# frequency_divider_1_3.net
KiCad netlist of a schematic drawn in EAGLE
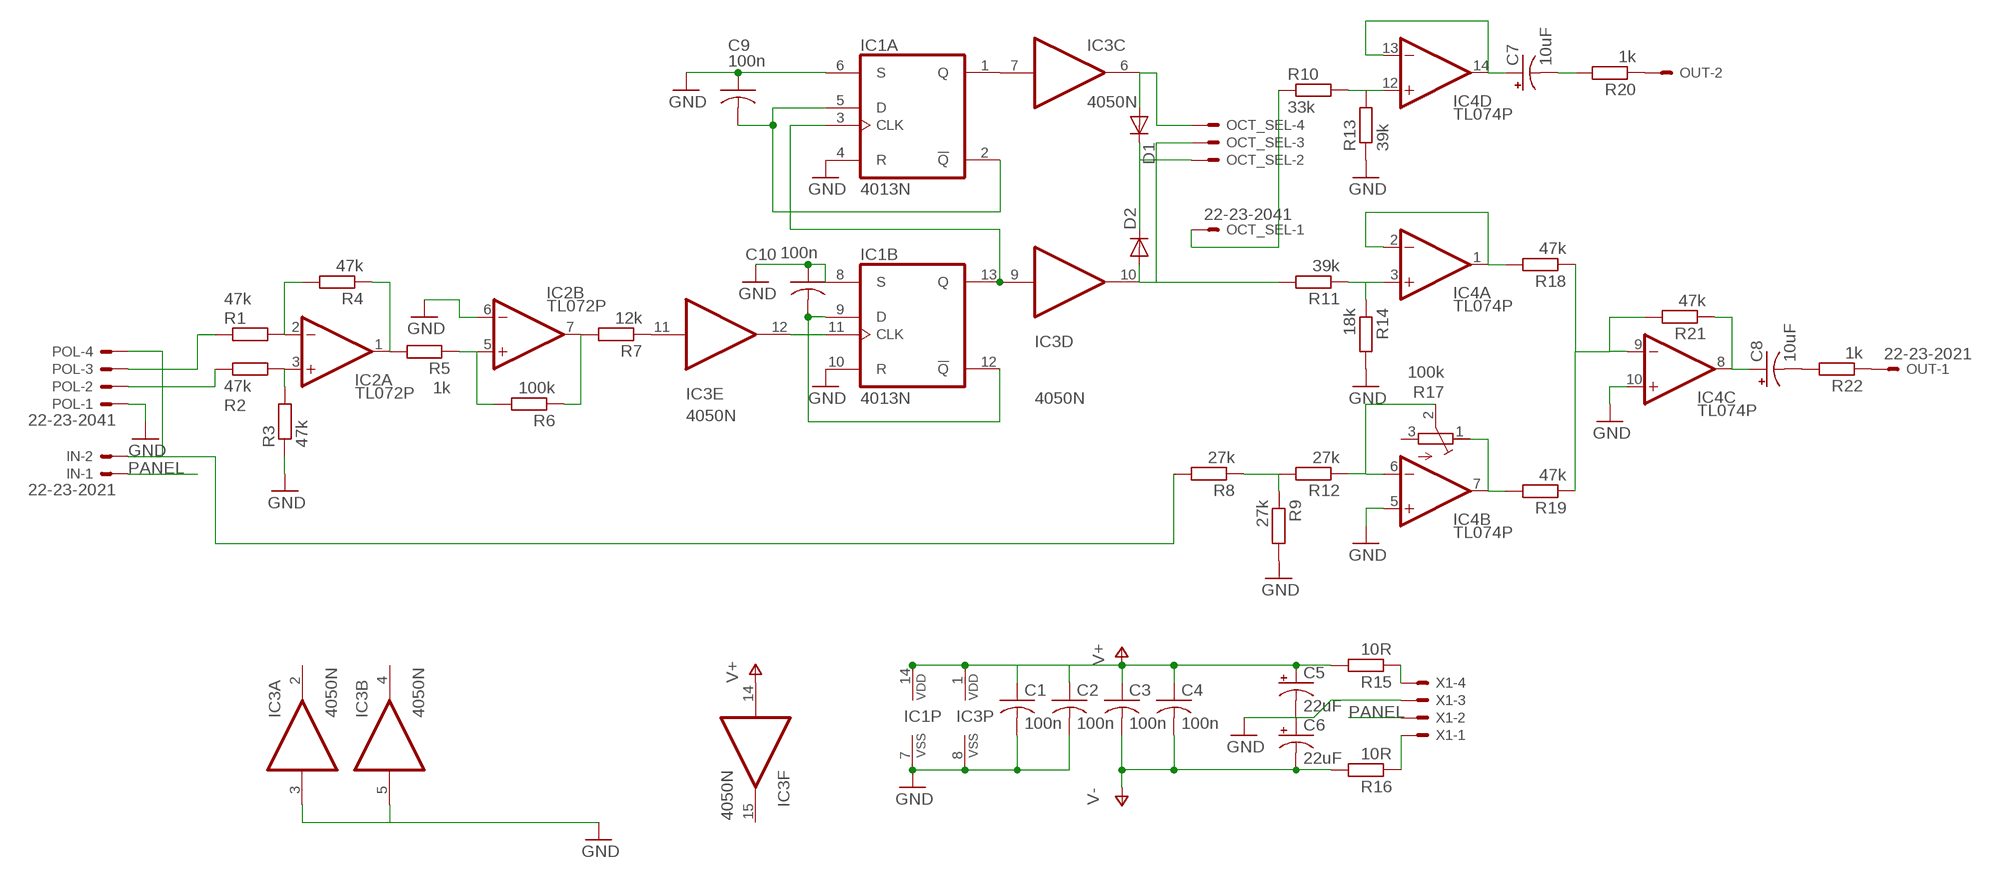
[diagram p0: schematic, sheet 1]

(export (version "E")
  (design (tool "Eeschema 10.0.6"))
  (components
    (comp (ref "C1")
      (value "100n")
      (footprint "eagle-import:C025-024X044")
      (libsource (lib "eagle-import") (part "C-US025-024X044"))
    )
    (comp (ref "C2")
      (value "100n")
      (footprint "eagle-import:C025-024X044")
      (libsource (lib "eagle-import") (part "C-US025-024X044"))
    )
    (comp (ref "C3")
      (value "100n")
      (footprint "eagle-import:C025-024X044")
      (libsource (lib "eagle-import") (part "C-US025-024X044"))
    )
    (comp (ref "C4")
      (value "100n")
      (footprint "eagle-import:C025-024X044")
      (libsource (lib "eagle-import") (part "C-US025-024X044"))
    )
    (comp (ref "C5")
      (value "22uF")
      (footprint "eagle-import:E2,5-5")
      (libsource (lib "eagle-import") (part "CPOL-USE2.5-5"))
    )
    (comp (ref "C6")
      (value "22uF")
      (footprint "eagle-import:E2,5-5")
      (libsource (lib "eagle-import") (part "CPOL-USE2.5-5"))
    )
    (comp (ref "C7")
      (value "10uF")
      (footprint "eagle-import:E2,5-5")
      (libsource (lib "eagle-import") (part "CPOL-USE2.5-5"))
    )
    (comp (ref "C8")
      (value "10uF")
      (footprint "eagle-import:E2,5-5")
      (libsource (lib "eagle-import") (part "CPOL-USE2.5-5"))
    )
    (comp (ref "C9")
      (value "100n")
      (footprint "eagle-import:C025-024X044")
      (libsource (lib "eagle-import") (part "C-US025-024X044"))
    )
    (comp (ref "C10")
      (value "100n")
      (footprint "eagle-import:C025-024X044")
      (libsource (lib "eagle-import") (part "C-US025-024X044"))
    )
    (comp (ref "D1")
      (value "DIODE-D-5")
      (footprint "eagle-import:D-5")
      (libsource (lib "eagle-import") (part "DIODE-D-5"))
    )
    (comp (ref "D2")
      (value "DIODE-D-5")
      (footprint "eagle-import:D-5")
      (libsource (lib "eagle-import") (part "DIODE-D-5"))
    )
    (comp (ref "IC1")
      (value "4013N")
      (footprint "eagle-import:DIL14")
      (libsource (lib "eagle-import") (part "4013N"))
    )
    (comp (ref "IC2")
      (value "TL072P")
      (footprint "eagle-import:DIL08")
      (libsource (lib "eagle-import") (part "TL072P"))
    )
    (comp (ref "IC3")
      (value "4050N")
      (footprint "eagle-import:DIL16")
      (libsource (lib "eagle-import") (part "4050N"))
    )
    (comp (ref "IC4")
      (value "TL074P")
      (footprint "eagle-import:DIL14")
      (libsource (lib "eagle-import") (part "TL074P"))
    )
    (comp (ref "IN")
      (value "22-23-2021")
      (footprint "eagle-import:22-23-2021")
      (fields (field (name "MF") "MOLEX"))
      (libsource (lib "eagle-import") (part "22-23-2021"))
    )
    (comp (ref "OCT_SEL")
      (value "22-23-2041")
      (footprint "eagle-import:22-23-2041")
      (fields (field (name "MF") "MOLEX"))
      (libsource (lib "eagle-import") (part "22-23-2041"))
    )
    (comp (ref "OUT")
      (value "22-23-2021")
      (footprint "eagle-import:22-23-2021")
      (fields (field (name "MF") "MOLEX"))
      (libsource (lib "eagle-import") (part "22-23-2021"))
    )
    (comp (ref "POL")
      (value "22-23-2041")
      (footprint "eagle-import:22-23-2041")
      (fields (field (name "MF") "MOLEX"))
      (libsource (lib "eagle-import") (part "22-23-2041"))
    )
    (comp (ref "R1")
      (value "47k")
      (footprint "eagle-import:0204_7")
      (libsource (lib "eagle-import") (part "R-EU_0204/7"))
    )
    (comp (ref "R2")
      (value "47k")
      (footprint "eagle-import:0204_7")
      (libsource (lib "eagle-import") (part "R-EU_0204/7"))
    )
    (comp (ref "R3")
      (value "47k")
      (footprint "eagle-import:0204_7")
      (libsource (lib "eagle-import") (part "R-EU_0204/7"))
    )
    (comp (ref "R4")
      (value "47k")
      (footprint "eagle-import:0204_7")
      (libsource (lib "eagle-import") (part "R-EU_0204/7"))
    )
    (comp (ref "R5")
      (value "1k")
      (footprint "eagle-import:0204_7")
      (libsource (lib "eagle-import") (part "R-EU_0204/7"))
    )
    (comp (ref "R6")
      (value "100k")
      (footprint "eagle-import:0204_7")
      (libsource (lib "eagle-import") (part "R-EU_0204/7"))
    )
    (comp (ref "R7")
      (value "12k")
      (footprint "eagle-import:0204_7")
      (libsource (lib "eagle-import") (part "R-EU_0204/7"))
    )
    (comp (ref "R8")
      (value "27k")
      (footprint "eagle-import:0204_7")
      (libsource (lib "eagle-import") (part "R-EU_0204/7"))
    )
    (comp (ref "R9")
      (value "27k")
      (footprint "eagle-import:0204_7")
      (libsource (lib "eagle-import") (part "R-EU_0204/7"))
    )
    (comp (ref "R10")
      (value "33k")
      (footprint "eagle-import:0204_7")
      (libsource (lib "eagle-import") (part "R-EU_0204/7"))
    )
    (comp (ref "R11")
      (value "39k")
      (footprint "eagle-import:0204_7")
      (libsource (lib "eagle-import") (part "resistor_R-EU_0204/7"))
    )
    (comp (ref "R12")
      (value "27k")
      (footprint "eagle-import:0204_7")
      (libsource (lib "eagle-import") (part "R-EU_0204/7"))
    )
    (comp (ref "R13")
      (value "39k")
      (footprint "eagle-import:0204_7")
      (libsource (lib "eagle-import") (part "R-EU_0204/7"))
    )
    (comp (ref "R14")
      (value "18k")
      (footprint "eagle-import:0204_7")
      (libsource (lib "eagle-import") (part "R-EU_0204/7"))
    )
    (comp (ref "R15")
      (value "10R")
      (footprint "eagle-import:0204_7")
      (libsource (lib "eagle-import") (part "R-EU_0204/7"))
    )
    (comp (ref "R16")
      (value "10R")
      (footprint "eagle-import:0204_7")
      (libsource (lib "eagle-import") (part "R-EU_0204/7"))
    )
    (comp (ref "R17")
      (value "100k")
      (footprint "eagle-import:RTRIMT93YA")
      (libsource (lib "eagle-import") (part "R-TRIMMT93YA"))
    )
    (comp (ref "R18")
      (value "47k")
      (footprint "eagle-import:0204_7")
      (libsource (lib "eagle-import") (part "R-EU_0204/7"))
    )
    (comp (ref "R19")
      (value "47k")
      (footprint "eagle-import:0204_7")
      (libsource (lib "eagle-import") (part "R-EU_0204/7"))
    )
    (comp (ref "R20")
      (value "1k")
      (footprint "eagle-import:0204_7")
      (libsource (lib "eagle-import") (part "R-EU_0204/7"))
    )
    (comp (ref "R21")
      (value "47k")
      (footprint "eagle-import:0204_7")
      (libsource (lib "eagle-import") (part "R-EU_0204/7"))
    )
    (comp (ref "R22")
      (value "1k")
      (footprint "eagle-import:0204_7")
      (libsource (lib "eagle-import") (part "R-EU_0204/7"))
    )
    (comp (ref "X1")
      (value "KK-156-4")
      (footprint "eagle-import:KK-156-4")
      (libsource (lib "eagle-import") (part "KK-156-4"))
    )
  )
  (nets
    (net (code "1") (name "/PANEL") (class "Default")
      (node (ref "IN") (pin "1") (pinfunction "S_1") (pintype "passive"))
      (node (ref "X1") (pin "2") (pinfunction "S_2") (pintype "passive"))
    )
    (net (code "2") (name "GND") (class "Default")
      (node (ref "C1") (pin "2") (pinfunction "2_2") (pintype "passive"))
      (node (ref "C10") (pin "1") (pinfunction "1_1") (pintype "passive"))
      (node (ref "C2") (pin "2") (pinfunction "2_2") (pintype "passive"))
      (node (ref "C5") (pin "-") (pinfunction "-_-") (pintype "passive"))
      (node (ref "C6") (pin "+") (pinfunction "+_+") (pintype "passive"))
      (node (ref "C9") (pin "1") (pinfunction "1_1") (pintype "passive"))
      (node (ref "IC1") (pin "10") (pinfunction "R_10") (pintype "input"))
      (node (ref "IC1") (pin "4") (pinfunction "R_4") (pintype "input"))
      (node (ref "IC1") (pin "6") (pinfunction "S_6") (pintype "input"))
      (node (ref "IC1") (pin "7") (pinfunction "VSS_7") (pintype "power_in"))
      (node (ref "IC1") (pin "8") (pinfunction "S_8") (pintype "input"))
      (node (ref "IC2") (pin "6") (pinfunction "-IN_6") (pintype "input"))
      (node (ref "IC3") (pin "3") (pinfunction "I_3") (pintype "input"))
      (node (ref "IC3") (pin "5") (pinfunction "I_5") (pintype "input"))
      (node (ref "IC3") (pin "8") (pinfunction "VSS_8") (pintype "power_in"))
      (node (ref "IC4") (pin "10") (pinfunction "+IN_10") (pintype "input"))
      (node (ref "IC4") (pin "5") (pinfunction "+IN_5") (pintype "input"))
      (node (ref "POL") (pin "1") (pinfunction "S_1") (pintype "passive"))
      (node (ref "R13") (pin "1") (pinfunction "1_1") (pintype "passive"))
      (node (ref "R14") (pin "2") (pinfunction "2_2") (pintype "passive"))
      (node (ref "R3") (pin "1") (pinfunction "1_1") (pintype "passive"))
      (node (ref "R9") (pin "2") (pinfunction "2_2") (pintype "passive"))
      (node (ref "X1") (pin "3") (pinfunction "S_3") (pintype "passive"))
    )
    (net (code "3") (name "Net-(C7-Pad-)") (class "Default")
      (node (ref "C7") (pin "-") (pinfunction "-_-") (pintype "passive"))
      (node (ref "R20") (pin "2") (pinfunction "2_2") (pintype "passive"))
    )
    (net (code "4") (name "Net-(C8-Pad-)") (class "Default")
      (node (ref "C8") (pin "-") (pinfunction "-_-") (pintype "passive"))
      (node (ref "R22") (pin "2") (pinfunction "2_2") (pintype "passive"))
    )
    (net (code "5") (name "Net-(IC1A-CLK)") (class "Default")
      (node (ref "IC1") (pin "13") (pinfunction "Q_13") (pintype "output"))
      (node (ref "IC1") (pin "3") (pinfunction "CLK_3") (pintype "input"))
      (node (ref "IC3") (pin "9") (pinfunction "I_9") (pintype "input"))
    )
    (net (code "6") (name "Net-(IC1A-D)") (class "Default")
      (node (ref "C9") (pin "2") (pinfunction "2_2") (pintype "passive"))
      (node (ref "IC1") (pin "2") (pinfunction "~{Q}_2") (pintype "output"))
      (node (ref "IC1") (pin "5") (pinfunction "D_5") (pintype "input"))
    )
    (net (code "7") (name "Net-(IC1A-Q)") (class "Default")
      (node (ref "IC1") (pin "1") (pinfunction "Q_1") (pintype "output"))
      (node (ref "IC3") (pin "7") (pinfunction "I_7") (pintype "input"))
    )
    (net (code "8") (name "Net-(IC1B-CLK)") (class "Default")
      (node (ref "IC1") (pin "11") (pinfunction "CLK_11") (pintype "input"))
      (node (ref "IC3") (pin "12") (pinfunction "O_12") (pintype "output"))
    )
    (net (code "9") (name "Net-(IC1B-D)") (class "Default")
      (node (ref "C10") (pin "2") (pinfunction "2_2") (pintype "passive"))
      (node (ref "IC1") (pin "12") (pinfunction "~{Q}_12") (pintype "output"))
      (node (ref "IC1") (pin "9") (pinfunction "D_9") (pintype "input"))
    )
    (net (code "10") (name "Net-(IC2A-+IN)") (class "Default")
      (node (ref "IC2") (pin "3") (pinfunction "+IN_3") (pintype "input"))
      (node (ref "R2") (pin "2") (pinfunction "2_2") (pintype "passive"))
      (node (ref "R3") (pin "2") (pinfunction "2_2") (pintype "passive"))
    )
    (net (code "11") (name "Net-(IC2A--IN)") (class "Default")
      (node (ref "IC2") (pin "2") (pinfunction "-IN_2") (pintype "input"))
      (node (ref "R1") (pin "2") (pinfunction "2_2") (pintype "passive"))
      (node (ref "R4") (pin "2") (pinfunction "2_2") (pintype "passive"))
    )
    (net (code "12") (name "Net-(IC2A-OUT)") (class "Default")
      (node (ref "IC2") (pin "1") (pinfunction "OUT_1") (pintype "output"))
      (node (ref "R4") (pin "1") (pinfunction "1_1") (pintype "passive"))
      (node (ref "R5") (pin "2") (pinfunction "2_2") (pintype "passive"))
    )
    (net (code "13") (name "Net-(IC2B-+IN)") (class "Default")
      (node (ref "IC2") (pin "5") (pinfunction "+IN_5") (pintype "input"))
      (node (ref "R5") (pin "1") (pinfunction "1_1") (pintype "passive"))
      (node (ref "R6") (pin "2") (pinfunction "2_2") (pintype "passive"))
    )
    (net (code "14") (name "Net-(IC2B-OUT)") (class "Default")
      (node (ref "IC2") (pin "7") (pinfunction "OUT_7") (pintype "output"))
      (node (ref "R6") (pin "1") (pinfunction "1_1") (pintype "passive"))
      (node (ref "R7") (pin "2") (pinfunction "2_2") (pintype "passive"))
    )
    (net (code "15") (name "Net-(IC3C-O)") (class "Default")
      (node (ref "D1") (pin "A") (pinfunction "A_A") (pintype "passive"))
      (node (ref "IC3") (pin "6") (pinfunction "O_6") (pintype "output"))
      (node (ref "OCT_SEL") (pin "4") (pinfunction "S_4") (pintype "passive"))
    )
    (net (code "16") (name "Net-(IC3D-O)") (class "Default")
      (node (ref "D2") (pin "A") (pinfunction "A_A") (pintype "passive"))
      (node (ref "IC3") (pin "10") (pinfunction "O_10") (pintype "output"))
      (node (ref "OCT_SEL") (pin "3") (pinfunction "S_3") (pintype "passive"))
      (node (ref "R11") (pin "2") (pinfunction "2_2") (pintype "passive"))
    )
    (net (code "17") (name "Net-(IC3E-I)") (class "Default")
      (node (ref "IC3") (pin "11") (pinfunction "I_11") (pintype "input"))
      (node (ref "R7") (pin "1") (pinfunction "1_1") (pintype "passive"))
    )
    (net (code "18") (name "Net-(IC4A-+IN)") (class "Default")
      (node (ref "IC4") (pin "3") (pinfunction "+IN_3") (pintype "input"))
      (node (ref "R11") (pin "1") (pinfunction "1_1") (pintype "passive"))
      (node (ref "R14") (pin "1") (pinfunction "1_1") (pintype "passive"))
    )
    (net (code "19") (name "Net-(IC4A--IN)") (class "Default")
      (node (ref "IC4") (pin "1") (pinfunction "OUT_1") (pintype "output"))
      (node (ref "IC4") (pin "2") (pinfunction "-IN_2") (pintype "input"))
      (node (ref "R18") (pin "2") (pinfunction "2_2") (pintype "passive"))
    )
    (net (code "20") (name "Net-(IC4B--IN)") (class "Default")
      (node (ref "IC4") (pin "6") (pinfunction "-IN_6") (pintype "input"))
      (node (ref "R12") (pin "1") (pinfunction "1_1") (pintype "passive"))
      (node (ref "R17") (pin "2") (pinfunction "S_2") (pintype "passive"))
    )
    (net (code "21") (name "Net-(IC4B-OUT)") (class "Default")
      (node (ref "IC4") (pin "7") (pinfunction "OUT_7") (pintype "output"))
      (node (ref "R17") (pin "1") (pinfunction "A_1") (pintype "passive"))
      (node (ref "R19") (pin "2") (pinfunction "2_2") (pintype "passive"))
    )
    (net (code "22") (name "Net-(IC4C--IN)") (class "Default")
      (node (ref "IC4") (pin "9") (pinfunction "-IN_9") (pintype "input"))
      (node (ref "R18") (pin "1") (pinfunction "1_1") (pintype "passive"))
      (node (ref "R19") (pin "1") (pinfunction "1_1") (pintype "passive"))
      (node (ref "R21") (pin "2") (pinfunction "2_2") (pintype "passive"))
    )
    (net (code "23") (name "Net-(IC4C-OUT)") (class "Default")
      (node (ref "C8") (pin "+") (pinfunction "+_+") (pintype "passive"))
      (node (ref "IC4") (pin "8") (pinfunction "OUT_8") (pintype "output"))
      (node (ref "R21") (pin "1") (pinfunction "1_1") (pintype "passive"))
    )
    (net (code "24") (name "Net-(IC4D-+IN)") (class "Default")
      (node (ref "IC4") (pin "12") (pinfunction "+IN_12") (pintype "input"))
      (node (ref "R10") (pin "2") (pinfunction "2_2") (pintype "passive"))
      (node (ref "R13") (pin "2") (pinfunction "2_2") (pintype "passive"))
    )
    (net (code "25") (name "Net-(IC4D--IN)") (class "Default")
      (node (ref "C7") (pin "+") (pinfunction "+_+") (pintype "passive"))
      (node (ref "IC4") (pin "13") (pinfunction "-IN_13") (pintype "input"))
      (node (ref "IC4") (pin "14") (pinfunction "OUT_14") (pintype "output"))
    )
    (net (code "26") (name "Net-(INB-S)") (class "Default")
      (node (ref "IN") (pin "2") (pinfunction "S_2") (pintype "passive"))
      (node (ref "POL") (pin "4") (pinfunction "S_4") (pintype "passive"))
      (node (ref "R8") (pin "2") (pinfunction "2_2") (pintype "passive"))
    )
    (net (code "27") (name "Net-(OCT_SELA-S)") (class "Default")
      (node (ref "OCT_SEL") (pin "1") (pinfunction "S_1") (pintype "passive"))
      (node (ref "R10") (pin "1") (pinfunction "1_1") (pintype "passive"))
    )
    (net (code "28") (name "Net-(OCT_SELB-S)") (class "Default")
      (node (ref "D1") (pin "C") (pinfunction "C_C") (pintype "passive"))
      (node (ref "D2") (pin "C") (pinfunction "C_C") (pintype "passive"))
      (node (ref "OCT_SEL") (pin "2") (pinfunction "S_2") (pintype "passive"))
    )
    (net (code "29") (name "Net-(OUTA-S)") (class "Default")
      (node (ref "OUT") (pin "1") (pinfunction "S_1") (pintype "passive"))
      (node (ref "R22") (pin "1") (pinfunction "1_1") (pintype "passive"))
    )
    (net (code "30") (name "Net-(OUTB-S)") (class "Default")
      (node (ref "OUT") (pin "2") (pinfunction "S_2") (pintype "passive"))
      (node (ref "R20") (pin "1") (pinfunction "1_1") (pintype "passive"))
    )
    (net (code "31") (name "Net-(POLB-S)") (class "Default")
      (node (ref "POL") (pin "2") (pinfunction "S_2") (pintype "passive"))
      (node (ref "R2") (pin "1") (pinfunction "1_1") (pintype "passive"))
    )
    (net (code "32") (name "Net-(POLC-S)") (class "Default")
      (node (ref "POL") (pin "3") (pinfunction "S_3") (pintype "passive"))
      (node (ref "R1") (pin "1") (pinfunction "1_1") (pintype "passive"))
    )
    (net (code "33") (name "Net-(R12-Pad2)") (class "Default")
      (node (ref "R12") (pin "2") (pinfunction "2_2") (pintype "passive"))
      (node (ref "R8") (pin "1") (pinfunction "1_1") (pintype "passive"))
      (node (ref "R9") (pin "1") (pinfunction "1_1") (pintype "passive"))
    )
    (net (code "34") (name "Net-(X1A-S)") (class "Default")
      (node (ref "R16") (pin "1") (pinfunction "1_1") (pintype "passive"))
      (node (ref "X1") (pin "1") (pinfunction "S_1") (pintype "passive"))
    )
    (net (code "35") (name "Net-(X1D-S)") (class "Default")
      (node (ref "R15") (pin "1") (pinfunction "1_1") (pintype "passive"))
      (node (ref "X1") (pin "4") (pinfunction "S_4") (pintype "passive"))
    )
    (net (code "36") (name "V+") (class "Default")
      (node (ref "C1") (pin "1") (pinfunction "1_1") (pintype "passive"))
      (node (ref "C2") (pin "1") (pinfunction "1_1") (pintype "passive"))
      (node (ref "C3") (pin "1") (pinfunction "1_1") (pintype "passive"))
      (node (ref "C4") (pin "1") (pinfunction "1_1") (pintype "passive"))
      (node (ref "C5") (pin "+") (pinfunction "+_+") (pintype "passive"))
      (node (ref "IC1") (pin "14") (pinfunction "VDD_14") (pintype "power_in"))
      (node (ref "IC3") (pin "1") (pinfunction "VDD_1") (pintype "power_in"))
      (node (ref "IC3") (pin "14") (pinfunction "I_14") (pintype "input"))
      (node (ref "R15") (pin "2") (pinfunction "2_2") (pintype "passive"))
    )
    (net (code "37") (name "V-") (class "Default")
      (node (ref "C3") (pin "2") (pinfunction "2_2") (pintype "passive"))
      (node (ref "C4") (pin "2") (pinfunction "2_2") (pintype "passive"))
      (node (ref "C6") (pin "-") (pinfunction "-_-") (pintype "passive"))
      (node (ref "R16") (pin "2") (pinfunction "2_2") (pintype "passive"))
    )
    (net (code "38") (name "unconnected-(IC3A-O-Pad2)") (class "Default")
      (node (ref "IC3") (pin "2") (pinfunction "O_2") (pintype "output"))
    )
    (net (code "39") (name "unconnected-(IC3B-O-Pad4)") (class "Default")
      (node (ref "IC3") (pin "4") (pinfunction "O_4") (pintype "output"))
    )
    (net (code "40") (name "unconnected-(IC3F-O-Pad15)") (class "Default")
      (node (ref "IC3") (pin "15") (pinfunction "O_15") (pintype "output"))
    )
    (net (code "41") (name "unconnected-(R17-E-Pad3)") (class "Default")
      (node (ref "R17") (pin "3") (pinfunction "E_3") (pintype "passive"))
    )
  )
)
